# LED_RGBSchDoc.net
KiCad netlist of a schematic drawn in Altium Designer
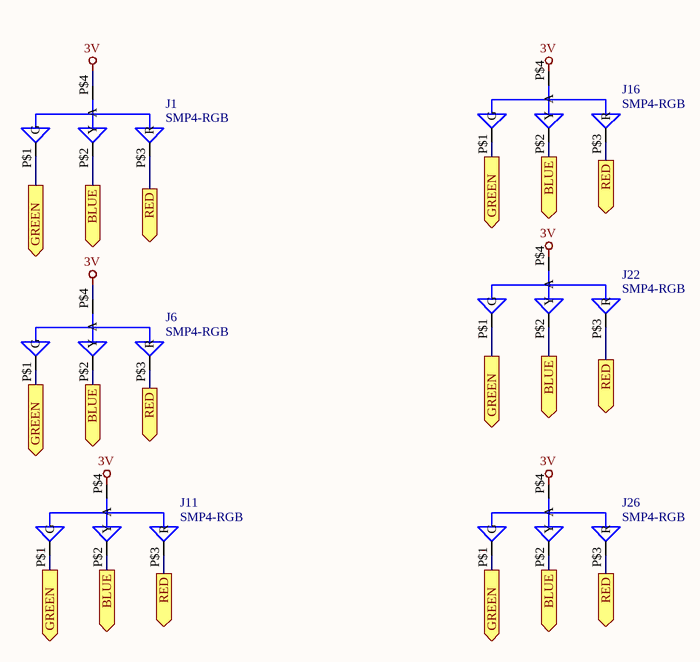
[diagram p0: LED RGBSchDoc.SchDoc]

(export (version "E")
  (design (tool "Eeschema 10.0.6"))
  (components
    (comp (ref "J1")
      (value "SMP4-RGB")
      (footprint "4-PLCC")
      (fields (field (name "MF") "Bivar Inc."))
      (libsource (lib "SMP4-RGB") (part "SMP4-RGB"))
    )
    (comp (ref "J6")
      (value "SMP4-RGB")
      (footprint "4-PLCC")
      (fields (field (name "MF") "Bivar Inc."))
      (libsource (lib "SMP4-RGB") (part "SMP4-RGB"))
    )
    (comp (ref "J11")
      (value "SMP4-RGB")
      (footprint "4-PLCC")
      (fields (field (name "MF") "Bivar Inc."))
      (libsource (lib "SMP4-RGB") (part "SMP4-RGB"))
    )
    (comp (ref "J16")
      (value "SMP4-RGB")
      (footprint "4-PLCC")
      (fields (field (name "MF") "Bivar Inc."))
      (libsource (lib "SMP4-RGB") (part "SMP4-RGB"))
    )
    (comp (ref "J22")
      (value "SMP4-RGB")
      (footprint "4-PLCC")
      (fields (field (name "MF") "Bivar Inc."))
      (libsource (lib "SMP4-RGB") (part "SMP4-RGB"))
    )
    (comp (ref "J26")
      (value "SMP4-RGB")
      (footprint "4-PLCC")
      (fields (field (name "MF") "Bivar Inc."))
      (libsource (lib "SMP4-RGB") (part "SMP4-RGB"))
    )
  )
  (nets
    (net (code "1") (name "/BLUE") (class "Default")
      (node (ref "J1") (pin "P$2") (pinfunction "Y_P$2") (pintype "bidirectional"))
      (node (ref "J11") (pin "P$2") (pinfunction "Y_P$2") (pintype "bidirectional"))
      (node (ref "J16") (pin "P$2") (pinfunction "Y_P$2") (pintype "bidirectional"))
      (node (ref "J22") (pin "P$2") (pinfunction "Y_P$2") (pintype "bidirectional"))
      (node (ref "J26") (pin "P$2") (pinfunction "Y_P$2") (pintype "bidirectional"))
      (node (ref "J6") (pin "P$2") (pinfunction "Y_P$2") (pintype "bidirectional"))
    )
    (net (code "2") (name "/GREEN") (class "Default")
      (node (ref "J1") (pin "P$1") (pinfunction "G_P$1") (pintype "bidirectional"))
      (node (ref "J11") (pin "P$1") (pinfunction "G_P$1") (pintype "bidirectional"))
      (node (ref "J16") (pin "P$1") (pinfunction "G_P$1") (pintype "bidirectional"))
      (node (ref "J22") (pin "P$1") (pinfunction "G_P$1") (pintype "bidirectional"))
      (node (ref "J26") (pin "P$1") (pinfunction "G_P$1") (pintype "bidirectional"))
      (node (ref "J6") (pin "P$1") (pinfunction "G_P$1") (pintype "bidirectional"))
    )
    (net (code "3") (name "/RED") (class "Default")
      (node (ref "J1") (pin "P$3") (pinfunction "R_P$3") (pintype "bidirectional"))
      (node (ref "J11") (pin "P$3") (pinfunction "R_P$3") (pintype "bidirectional"))
      (node (ref "J16") (pin "P$3") (pinfunction "R_P$3") (pintype "bidirectional"))
      (node (ref "J22") (pin "P$3") (pinfunction "R_P$3") (pintype "bidirectional"))
      (node (ref "J26") (pin "P$3") (pinfunction "R_P$3") (pintype "bidirectional"))
      (node (ref "J6") (pin "P$3") (pinfunction "R_P$3") (pintype "bidirectional"))
    )
    (net (code "4") (name "3V") (class "Default")
      (node (ref "J1") (pin "P$4") (pinfunction "A_P$4") (pintype "bidirectional"))
      (node (ref "J11") (pin "P$4") (pinfunction "A_P$4") (pintype "bidirectional"))
      (node (ref "J16") (pin "P$4") (pinfunction "A_P$4") (pintype "bidirectional"))
      (node (ref "J22") (pin "P$4") (pinfunction "A_P$4") (pintype "bidirectional"))
      (node (ref "J26") (pin "P$4") (pinfunction "A_P$4") (pintype "bidirectional"))
      (node (ref "J6") (pin "P$4") (pinfunction "A_P$4") (pintype "bidirectional"))
    )
  )
)
